# LC_LPF3.net
KiCad netlist of a schematic drawn in Altium Designer
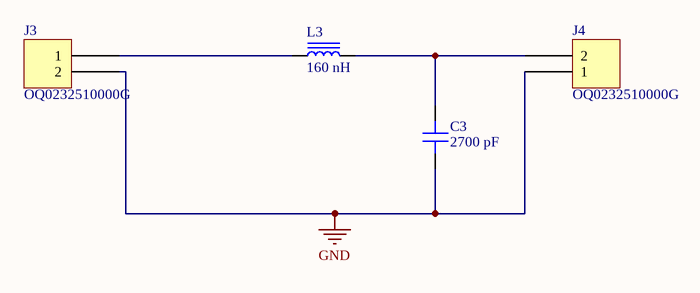
[diagram p0: LC_LPF3.SchDoc]

(export (version "E")
  (design (tool "Eeschema 10.0.6"))
  (components
    (comp (ref "C3")
      (value "2700 pF")
      (footprint "CAP 0603_1608")
      (description "CAP CER 2700PF 25V NP0 0603")
      (fields (field (name "PART NUMBER") "C0603C272F3GAC7867") (field (name "MANUFACTURER") "KEMET"))
      (libsource (lib "Celestial Altium Library - altium_library") (part "Capacitor"))
    )
    (comp (ref "J3")
      (value "OQ0232510000G")
      (footprint "FCI 06-381-2PIN")
      (description "TERM BLOCK HDR 2POS 90DEG 3.81MM")
      (fields (field (name "MANUFACTURER") "Amphenol Anytek"))
      (libsource (lib "Celestial Altium Library - altium_library") (part "2 Pin"))
    )
    (comp (ref "J4")
      (value "OQ0232510000G")
      (footprint "FCI 06-381-2PIN")
      (description "TERM BLOCK HDR 2POS 90DEG 3.81MM")
      (fields (field (name "MANUFACTURER") "Amphenol Anytek"))
      (libsource (lib "") (part "2 Pin_1"))
    )
    (comp (ref "L3")
      (value "160 nH")
      (footprint "IND 0402_1005 RF WW")
      (description "FIXED IND 160NH 480MA 330MOHM SM")
      (fields
        (field (name "PART NUMBER") "LQW15CNR16J00D")
        (field (name "MANUFACTURER") "Murata Electronics")
      )
      (libsource (lib "Celestial Altium Library - altium_library") (part "Inductor"))
    )
  )
  (nets
    (net (code "1") (name "GND") (class "Default")
      (node (ref "C3") (pin "1") (pinfunction "1_1") (pintype "passive"))
      (node (ref "J3") (pin "2") (pinfunction "2_2") (pintype "passive"))
      (node (ref "J4") (pin "1") (pinfunction "1_1") (pintype "passive"))
    )
    (net (code "2") (name "Net-(C3-Pad2)") (class "Default")
      (node (ref "C3") (pin "2") (pinfunction "2_2") (pintype "passive"))
      (node (ref "J4") (pin "2") (pinfunction "2_2") (pintype "passive"))
      (node (ref "L3") (pin "2") (pinfunction "2_2") (pintype "passive"))
    )
    (net (code "3") (name "Net-(J3-Pad1)") (class "Default")
      (node (ref "J3") (pin "1") (pinfunction "1_1") (pintype "passive"))
      (node (ref "L3") (pin "1") (pinfunction "1_1") (pintype "passive"))
    )
  )
)
